# 01_-_POWER.net
KiCad netlist of a schematic drawn in Altium Designer
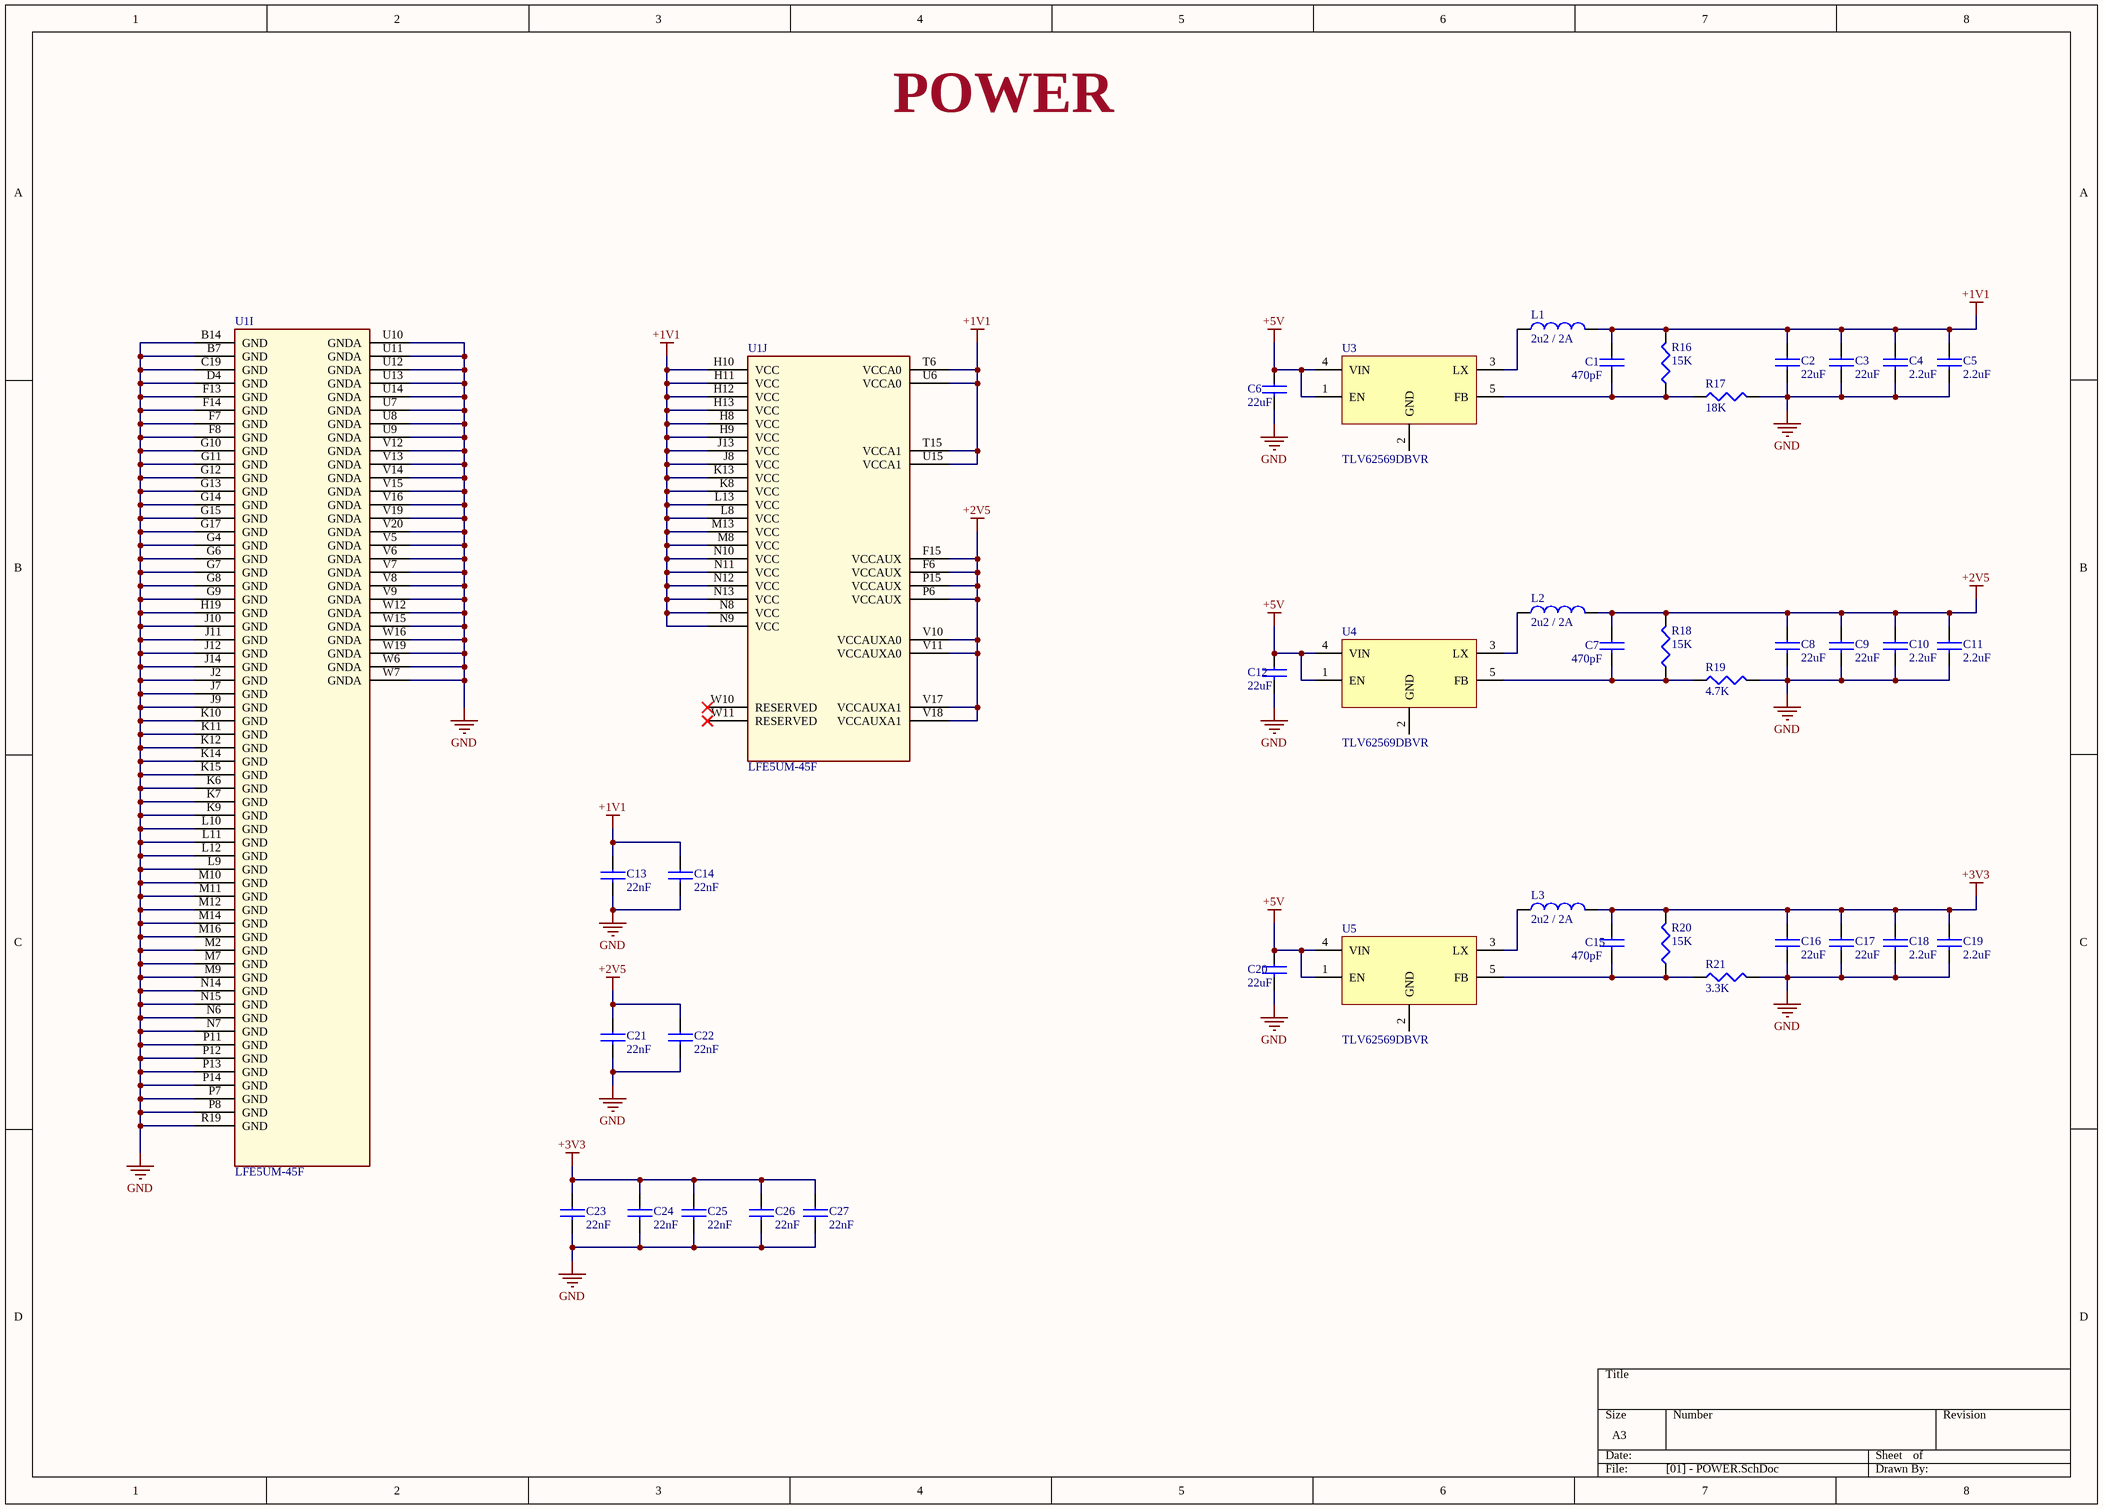
[diagram p0: [01] - POWER.SchDoc]

(export (version "E")
  (design (tool "Eeschema 10.0.6"))
  (components
    (comp (ref "C1")
      (value "470pF")
      (footprint "C0603")
      (fields
        (field (name "MANUFACTURER") "KEMET")
        (field (name "MANUFACTURER PART NUMBER") "C0603C471K3RACTU")
        (field (name "TOLERANCE") "10%")
      )
      (libsource (lib "ECP5_V2") (part "C0603C471K3RACTU"))
    )
    (comp (ref "C2")
      (value "22uF")
      (footprint "C0805")
      (description "CAP CER 22UF 6.3V X5R 0805")
      (fields
        (field (name "MANUFACTURER") "Samsung")
        (field (name "MANUFACTURER PART NUMBER") "CL21A226MQCLRNC")
      )
      (libsource (lib "ECP5_V2") (part "CL21A226MQCLRNC"))
    )
    (comp (ref "C3")
      (value "22uF")
      (footprint "C0805")
      (description "CAP CER 22UF 6.3V X5R 0805")
      (fields
        (field (name "MANUFACTURER") "Samsung")
        (field (name "MANUFACTURER PART NUMBER") "CL21A226MQCLRNC")
      )
      (libsource (lib "ECP5_V2") (part "CL21A226MQCLRNC"))
    )
    (comp (ref "C4")
      (value "2.2uF")
      (footprint "C0805")
      (description "Ceramic capacitor SMD 0805 2.2 µF 25 V 10 %")
      (fields
        (field (name "MANUFACTURER") "Samsung")
        (field (name "MANUFACTURER PART NUMBER") "CL21A225KAFNNNG")
      )
      (libsource (lib "ECP5_V2") (part "CL21A225KAFNNNG"))
    )
    (comp (ref "C5")
      (value "2.2uF")
      (footprint "C0805")
      (description "Ceramic capacitor SMD 0805 2.2 µF 25 V 10 %")
      (fields
        (field (name "MANUFACTURER") "Samsung")
        (field (name "MANUFACTURER PART NUMBER") "CL21A225KAFNNNG")
      )
      (libsource (lib "ECP5_V2") (part "CL21A225KAFNNNG"))
    )
    (comp (ref "C6")
      (value "22uF")
      (footprint "C0805")
      (description "CAP CER 22UF 6.3V X5R 0805")
      (fields
        (field (name "MANUFACTURER") "Samsung")
        (field (name "MANUFACTURER PART NUMBER") "CL21A226MQCLRNC")
      )
      (libsource (lib "ECP5_V2") (part "CL21A226MQCLRNC"))
    )
    (comp (ref "C7")
      (value "470pF")
      (footprint "C0603")
      (fields
        (field (name "MANUFACTURER") "KEMET")
        (field (name "MANUFACTURER PART NUMBER") "C0603C471K3RACTU")
        (field (name "TOLERANCE") "10%")
      )
      (libsource (lib "ECP5_V2") (part "C0603C471K3RACTU"))
    )
    (comp (ref "C8")
      (value "22uF")
      (footprint "C0805")
      (description "CAP CER 22UF 6.3V X5R 0805")
      (fields
        (field (name "MANUFACTURER") "Samsung")
        (field (name "MANUFACTURER PART NUMBER") "CL21A226MQCLRNC")
      )
      (libsource (lib "ECP5_V2") (part "CL21A226MQCLRNC"))
    )
    (comp (ref "C9")
      (value "22uF")
      (footprint "C0805")
      (description "CAP CER 22UF 6.3V X5R 0805")
      (fields
        (field (name "MANUFACTURER") "Samsung")
        (field (name "MANUFACTURER PART NUMBER") "CL21A226MQCLRNC")
      )
      (libsource (lib "ECP5_V2") (part "CL21A226MQCLRNC"))
    )
    (comp (ref "C10")
      (value "2.2uF")
      (footprint "C0805")
      (description "Ceramic capacitor SMD 0805 2.2 µF 25 V 10 %")
      (fields
        (field (name "MANUFACTURER") "Samsung")
        (field (name "MANUFACTURER PART NUMBER") "CL21A225KAFNNNG")
      )
      (libsource (lib "ECP5_V2") (part "CL21A225KAFNNNG"))
    )
    (comp (ref "C11")
      (value "2.2uF")
      (footprint "C0805")
      (description "Ceramic capacitor SMD 0805 2.2 µF 25 V 10 %")
      (fields
        (field (name "MANUFACTURER") "Samsung")
        (field (name "MANUFACTURER PART NUMBER") "CL21A225KAFNNNG")
      )
      (libsource (lib "ECP5_V2") (part "CL21A225KAFNNNG"))
    )
    (comp (ref "C12")
      (value "22uF")
      (footprint "C0805")
      (description "CAP CER 22UF 6.3V X5R 0805")
      (fields
        (field (name "MANUFACTURER") "Samsung")
        (field (name "MANUFACTURER PART NUMBER") "CL21A226MQCLRNC")
      )
      (libsource (lib "ECP5_V2") (part "CL21A226MQCLRNC"))
    )
    (comp (ref "C13")
      (value "22nF")
      (footprint "C0603")
      (description "Feed Through Capacitors 22nF X7R 20% 25V")
      (fields
        (field (name "MANUFACTURER") "Yageo")
        (field (name "MANUFACTURER PART NUMBER") "CX0603MRX7R8BB223")
      )
      (libsource (lib "ECP5_V2") (part "CX0603MRX7R8BB223"))
    )
    (comp (ref "C14")
      (value "22nF")
      (footprint "C0603")
      (description "Feed Through Capacitors 22nF X7R 20% 25V")
      (fields
        (field (name "MANUFACTURER") "Yageo")
        (field (name "MANUFACTURER PART NUMBER") "CX0603MRX7R8BB223")
      )
      (libsource (lib "ECP5_V2") (part "CX0603MRX7R8BB223"))
    )
    (comp (ref "C15")
      (value "470pF")
      (footprint "C0603")
      (fields
        (field (name "MANUFACTURER") "KEMET")
        (field (name "MANUFACTURER PART NUMBER") "C0603C471K3RACTU")
        (field (name "TOLERANCE") "10%")
      )
      (libsource (lib "ECP5_V2") (part "C0603C471K3RACTU"))
    )
    (comp (ref "C16")
      (value "22uF")
      (footprint "C0805")
      (description "CAP CER 22UF 6.3V X5R 0805")
      (fields
        (field (name "MANUFACTURER") "Samsung")
        (field (name "MANUFACTURER PART NUMBER") "CL21A226MQCLRNC")
      )
      (libsource (lib "ECP5_V2") (part "CL21A226MQCLRNC"))
    )
    (comp (ref "C17")
      (value "22uF")
      (footprint "C0805")
      (description "CAP CER 22UF 6.3V X5R 0805")
      (fields
        (field (name "MANUFACTURER") "Samsung")
        (field (name "MANUFACTURER PART NUMBER") "CL21A226MQCLRNC")
      )
      (libsource (lib "ECP5_V2") (part "CL21A226MQCLRNC"))
    )
    (comp (ref "C18")
      (value "2.2uF")
      (footprint "C0805")
      (description "Ceramic capacitor SMD 0805 2.2 µF 25 V 10 %")
      (fields
        (field (name "MANUFACTURER") "Samsung")
        (field (name "MANUFACTURER PART NUMBER") "CL21A225KAFNNNG")
      )
      (libsource (lib "ECP5_V2") (part "CL21A225KAFNNNG"))
    )
    (comp (ref "C19")
      (value "2.2uF")
      (footprint "C0805")
      (description "Ceramic capacitor SMD 0805 2.2 µF 25 V 10 %")
      (fields
        (field (name "MANUFACTURER") "Samsung")
        (field (name "MANUFACTURER PART NUMBER") "CL21A225KAFNNNG")
      )
      (libsource (lib "ECP5_V2") (part "CL21A225KAFNNNG"))
    )
    (comp (ref "C20")
      (value "22uF")
      (footprint "C0805")
      (description "CAP CER 22UF 6.3V X5R 0805")
      (fields
        (field (name "MANUFACTURER") "Samsung")
        (field (name "MANUFACTURER PART NUMBER") "CL21A226MQCLRNC")
      )
      (libsource (lib "ECP5_V2") (part "CL21A226MQCLRNC"))
    )
    (comp (ref "C21")
      (value "22nF")
      (footprint "C0603")
      (description "Feed Through Capacitors 22nF X7R 20% 25V")
      (fields
        (field (name "MANUFACTURER") "Yageo")
        (field (name "MANUFACTURER PART NUMBER") "CX0603MRX7R8BB223")
      )
      (libsource (lib "ECP5_V2") (part "CX0603MRX7R8BB223"))
    )
    (comp (ref "C22")
      (value "22nF")
      (footprint "C0603")
      (description "Feed Through Capacitors 22nF X7R 20% 25V")
      (fields
        (field (name "MANUFACTURER") "Yageo")
        (field (name "MANUFACTURER PART NUMBER") "CX0603MRX7R8BB223")
      )
      (libsource (lib "ECP5_V2") (part "CX0603MRX7R8BB223"))
    )
    (comp (ref "C23")
      (value "22nF")
      (footprint "C0603")
      (description "Feed Through Capacitors 22nF X7R 20% 25V")
      (fields
        (field (name "MANUFACTURER") "Yageo")
        (field (name "MANUFACTURER PART NUMBER") "CX0603MRX7R8BB223")
      )
      (libsource (lib "ECP5_V2") (part "CX0603MRX7R8BB223"))
    )
    (comp (ref "C24")
      (value "22nF")
      (footprint "C0603")
      (description "Feed Through Capacitors 22nF X7R 20% 25V")
      (fields
        (field (name "MANUFACTURER") "Yageo")
        (field (name "MANUFACTURER PART NUMBER") "CX0603MRX7R8BB223")
      )
      (libsource (lib "ECP5_V2") (part "CX0603MRX7R8BB223"))
    )
    (comp (ref "C25")
      (value "22nF")
      (footprint "C0603")
      (description "Feed Through Capacitors 22nF X7R 20% 25V")
      (fields
        (field (name "MANUFACTURER") "Yageo")
        (field (name "MANUFACTURER PART NUMBER") "CX0603MRX7R8BB223")
      )
      (libsource (lib "ECP5_V2") (part "CX0603MRX7R8BB223"))
    )
    (comp (ref "C26")
      (value "22nF")
      (footprint "C0603")
      (description "Feed Through Capacitors 22nF X7R 20% 25V")
      (fields
        (field (name "MANUFACTURER") "Yageo")
        (field (name "MANUFACTURER PART NUMBER") "CX0603MRX7R8BB223")
      )
      (libsource (lib "ECP5_V2") (part "CX0603MRX7R8BB223"))
    )
    (comp (ref "C27")
      (value "22nF")
      (footprint "C0603")
      (description "Feed Through Capacitors 22nF X7R 20% 25V")
      (fields
        (field (name "MANUFACTURER") "Yageo")
        (field (name "MANUFACTURER PART NUMBER") "CX0603MRX7R8BB223")
      )
      (libsource (lib "ECP5_V2") (part "CX0603MRX7R8BB223"))
    )
    (comp (ref "L1")
      (value "2u2 / 2A")
      (footprint "C1210_IND")
      (description "FIXED IND 2.2UH 2A 80 MOHM SMD")
      (fields
        (field (name "MANUFACTURER") "KEMET")
        (field (name "MANUFACTURER PART NUMBER") "L1210R2R2MDWIT")
      )
      (libsource (lib "ECP5_V2") (part "L1210R2R2MDWIT"))
    )
    (comp (ref "L2")
      (value "2u2 / 2A")
      (footprint "C1210_IND")
      (description "FIXED IND 2.2UH 2A 80 MOHM SMD")
      (fields
        (field (name "MANUFACTURER") "KEMET")
        (field (name "MANUFACTURER PART NUMBER") "L1210R2R2MDWIT")
      )
      (libsource (lib "ECP5_V2") (part "L1210R2R2MDWIT"))
    )
    (comp (ref "L3")
      (value "2u2 / 2A")
      (footprint "C1210_IND")
      (description "FIXED IND 2.2UH 2A 80 MOHM SMD")
      (fields
        (field (name "MANUFACTURER") "KEMET")
        (field (name "MANUFACTURER PART NUMBER") "L1210R2R2MDWIT")
      )
      (libsource (lib "ECP5_V2") (part "L1210R2R2MDWIT"))
    )
    (comp (ref "R16")
      (value "15K")
      (footprint "R0603")
      (description "Res Thick Film 0603 15K Ohm 1% 1/10W ?100ppm/?C Molded SMD Paper T/R")
      (fields
        (field (name "MANUFACTURER") "Yageo")
        (field (name "MANUFACTURER PART NUMBER") "RC0603FR-0715KL")
      )
      (libsource (lib "ECP5_V2") (part "RC0603FR-0715KL"))
    )
    (comp (ref "R17")
      (value "18K")
      (footprint "R0603")
      (fields
        (field (name "MANUFACTURER") "Yageo")
        (field (name "MANUFACTURER PART NUMBER") "RC0603FR-0718KL")
        (field (name "TOLERANCE") "1%")
      )
      (libsource (lib "ECP5_V2") (part "RC0603FR-0718KL"))
    )
    (comp (ref "R18")
      (value "15K")
      (footprint "R0603")
      (description "Res Thick Film 0603 15K Ohm 1% 1/10W ?100ppm/?C Molded SMD Paper T/R")
      (fields
        (field (name "MANUFACTURER") "Yageo")
        (field (name "MANUFACTURER PART NUMBER") "RC0603FR-0715KL")
      )
      (libsource (lib "ECP5_V2") (part "RC0603FR-0715KL"))
    )
    (comp (ref "R19")
      (value "4.7K")
      (footprint "R0603")
      (description "RES SMD 4.7K OHM 1% 1/10W 0603")
      (fields
        (field (name "MANUFACTURER") "Yageo")
        (field (name "MANUFACTURER PART NUMBER") "RC0603FR-074K7L")
      )
      (libsource (lib "ECP5_V2") (part "RC0603FR-074K7L"))
    )
    (comp (ref "R20")
      (value "15K")
      (footprint "R0603")
      (description "Res Thick Film 0603 15K Ohm 1% 1/10W ?100ppm/?C Molded SMD Paper T/R")
      (fields
        (field (name "MANUFACTURER") "Yageo")
        (field (name "MANUFACTURER PART NUMBER") "RC0603FR-0715KL")
      )
      (libsource (lib "ECP5_V2") (part "RC0603FR-0715KL"))
    )
    (comp (ref "R21")
      (value "3.3K")
      (footprint "R0603")
      (fields
        (field (name "MANUFACTURER") "Yageo")
        (field (name "MANUFACTURER PART NUMBER") "RC0603FR-073K3L")
        (field (name "TOLERANCE") "1%")
      )
      (libsource (lib "ECP5_V2") (part "RC0603FR-073K3L"))
    )
    (comp (ref "U1")
      (value "LFE5UM-45F")
      (footprint "LFE5BG381")
      (description "ECP5 Series 44 K LUTs 203 I/O 1.1 V Slow Surface Mount FPGA - CABGA-381")
      (fields
        (field (name "MANUFACTURER") "Lattice Semiconductor")
        (field (name "MANUFACTURER PART NUMBER") "LFE5UM-45F-6BG381C")
      )
      (libsource (lib "ECP5_V2") (part "LFE5UM-45F-6BG381C"))
    )
    (comp (ref "U3")
      (value "TLV62569DBVR")
      (footprint "SOT95P370X145-5N")
      (description "1-A HIGH EFFICIENCY STEP-DOWN")
      (fields (field (name "MANUFACTURER") "Texas Instruments"))
      (libsource (lib "ECP5_V2") (part "TLV62569DBVR"))
    )
    (comp (ref "U4")
      (value "TLV62569DBVR")
      (footprint "SOT95P370X145-5N")
      (description "1-A HIGH EFFICIENCY STEP-DOWN")
      (fields (field (name "MANUFACTURER") "Texas Instruments"))
      (libsource (lib "ECP5_V2") (part "TLV62569DBVR"))
    )
    (comp (ref "U5")
      (value "TLV62569DBVR")
      (footprint "SOT95P370X145-5N")
      (description "1-A HIGH EFFICIENCY STEP-DOWN")
      (fields (field (name "MANUFACTURER") "Texas Instruments"))
      (libsource (lib "ECP5_V2") (part "TLV62569DBVR"))
    )
  )
  (nets
    (net (code "1") (name "+1V1") (class "Default")
      (node (ref "C1") (pin "1") (pinfunction "1_1") (pintype "passive"))
      (node (ref "C13") (pin "1") (pinfunction "1_1") (pintype "passive"))
      (node (ref "C14") (pin "1") (pinfunction "1_1") (pintype "passive"))
      (node (ref "C2") (pin "1") (pinfunction "1_1") (pintype "passive"))
      (node (ref "C3") (pin "1") (pinfunction "1_1") (pintype "passive"))
      (node (ref "C4") (pin "1") (pinfunction "1_1") (pintype "passive"))
      (node (ref "C5") (pin "1") (pinfunction "1_1") (pintype "passive"))
      (node (ref "L1") (pin "2") (pinfunction "2_2") (pintype "passive"))
      (node (ref "R16") (pin "2") (pinfunction "2_2") (pintype "passive"))
      (node (ref "U1") (pin "H10") (pinfunction "VCC_H10") (pintype "power_in"))
      (node (ref "U1") (pin "H11") (pinfunction "VCC_H11") (pintype "power_in"))
      (node (ref "U1") (pin "H12") (pinfunction "VCC_H12") (pintype "power_in"))
      (node (ref "U1") (pin "H13") (pinfunction "VCC_H13") (pintype "power_in"))
      (node (ref "U1") (pin "H8") (pinfunction "VCC_H8") (pintype "power_in"))
      (node (ref "U1") (pin "H9") (pinfunction "VCC_H9") (pintype "power_in"))
      (node (ref "U1") (pin "J13") (pinfunction "VCC_J13") (pintype "power_in"))
      (node (ref "U1") (pin "J8") (pinfunction "VCC_J8") (pintype "power_in"))
      (node (ref "U1") (pin "K13") (pinfunction "VCC_K13") (pintype "power_in"))
      (node (ref "U1") (pin "K8") (pinfunction "VCC_K8") (pintype "power_in"))
      (node (ref "U1") (pin "L13") (pinfunction "VCC_L13") (pintype "power_in"))
      (node (ref "U1") (pin "L8") (pinfunction "VCC_L8") (pintype "power_in"))
      (node (ref "U1") (pin "M13") (pinfunction "VCC_M13") (pintype "power_in"))
      (node (ref "U1") (pin "M8") (pinfunction "VCC_M8") (pintype "power_in"))
      (node (ref "U1") (pin "N10") (pinfunction "VCC_N10") (pintype "power_in"))
      (node (ref "U1") (pin "N11") (pinfunction "VCC_N11") (pintype "power_in"))
      (node (ref "U1") (pin "N12") (pinfunction "VCC_N12") (pintype "power_in"))
      (node (ref "U1") (pin "N13") (pinfunction "VCC_N13") (pintype "power_in"))
      (node (ref "U1") (pin "N8") (pinfunction "VCC_N8") (pintype "power_in"))
      (node (ref "U1") (pin "N9") (pinfunction "VCC_N9") (pintype "power_in"))
      (node (ref "U1") (pin "T15") (pinfunction "VCCA1_T15") (pintype "power_in"))
      (node (ref "U1") (pin "T6") (pinfunction "VCCA0_T6") (pintype "power_in"))
      (node (ref "U1") (pin "U15") (pinfunction "VCCA1_U15") (pintype "power_in"))
      (node (ref "U1") (pin "U6") (pinfunction "VCCA0_U6") (pintype "power_in"))
    )
    (net (code "2") (name "+2V5") (class "Default")
      (node (ref "C10") (pin "1") (pinfunction "1_1") (pintype "passive"))
      (node (ref "C11") (pin "1") (pinfunction "1_1") (pintype "passive"))
      (node (ref "C21") (pin "1") (pinfunction "1_1") (pintype "passive"))
      (node (ref "C22") (pin "1") (pinfunction "1_1") (pintype "passive"))
      (node (ref "C7") (pin "1") (pinfunction "1_1") (pintype "passive"))
      (node (ref "C8") (pin "1") (pinfunction "1_1") (pintype "passive"))
      (node (ref "C9") (pin "1") (pinfunction "1_1") (pintype "passive"))
      (node (ref "L2") (pin "2") (pinfunction "2_2") (pintype "passive"))
      (node (ref "R18") (pin "2") (pinfunction "2_2") (pintype "passive"))
      (node (ref "U1") (pin "F15") (pinfunction "VCCAUX_F15") (pintype "power_in"))
      (node (ref "U1") (pin "F6") (pinfunction "VCCAUX_F6") (pintype "power_in"))
      (node (ref "U1") (pin "P15") (pinfunction "VCCAUX_P15") (pintype "power_in"))
      (node (ref "U1") (pin "P6") (pinfunction "VCCAUX_P6") (pintype "power_in"))
      (node (ref "U1") (pin "V10") (pinfunction "VCCAUXA0_V10") (pintype "power_in"))
      (node (ref "U1") (pin "V11") (pinfunction "VCCAUXA0_V11") (pintype "power_in"))
      (node (ref "U1") (pin "V17") (pinfunction "VCCAUXA1_V17") (pintype "power_in"))
      (node (ref "U1") (pin "V18") (pinfunction "VCCAUXA1_V18") (pintype "power_in"))
    )
    (net (code "3") (name "+3V3") (class "Default")
      (node (ref "C15") (pin "1") (pinfunction "1_1") (pintype "passive"))
      (node (ref "C16") (pin "1") (pinfunction "1_1") (pintype "passive"))
      (node (ref "C17") (pin "1") (pinfunction "1_1") (pintype "passive"))
      (node (ref "C18") (pin "1") (pinfunction "1_1") (pintype "passive"))
      (node (ref "C19") (pin "1") (pinfunction "1_1") (pintype "passive"))
      (node (ref "C23") (pin "1") (pinfunction "1_1") (pintype "passive"))
      (node (ref "C24") (pin "1") (pinfunction "1_1") (pintype "passive"))
      (node (ref "C25") (pin "1") (pinfunction "1_1") (pintype "passive"))
      (node (ref "C26") (pin "1") (pinfunction "1_1") (pintype "passive"))
      (node (ref "C27") (pin "1") (pinfunction "1_1") (pintype "passive"))
      (node (ref "L3") (pin "2") (pinfunction "2_2") (pintype "passive"))
      (node (ref "R20") (pin "2") (pinfunction "2_2") (pintype "passive"))
    )
    (net (code "4") (name "+5V") (class "Default")
      (node (ref "C12") (pin "1") (pinfunction "1_1") (pintype "passive"))
      (node (ref "C20") (pin "1") (pinfunction "1_1") (pintype "passive"))
      (node (ref "C6") (pin "1") (pinfunction "1_1") (pintype "passive"))
      (node (ref "U3") (pin "1") (pinfunction "EN_1") (pintype "passive"))
      (node (ref "U3") (pin "4") (pinfunction "VIN_4") (pintype "passive"))
      (node (ref "U4") (pin "1") (pinfunction "EN_1") (pintype "passive"))
      (node (ref "U4") (pin "4") (pinfunction "VIN_4") (pintype "passive"))
      (node (ref "U5") (pin "1") (pinfunction "EN_1") (pintype "passive"))
      (node (ref "U5") (pin "4") (pinfunction "VIN_4") (pintype "passive"))
    )
    (net (code "5") (name "GND") (class "Default")
      (node (ref "C10") (pin "2") (pinfunction "2_2") (pintype "passive"))
      (node (ref "C11") (pin "2") (pinfunction "2_2") (pintype "passive"))
      (node (ref "C12") (pin "2") (pinfunction "2_2") (pintype "passive"))
      (node (ref "C13") (pin "2") (pinfunction "2_2") (pintype "passive"))
      (node (ref "C14") (pin "2") (pinfunction "2_2") (pintype "passive"))
      (node (ref "C16") (pin "2") (pinfunction "2_2") (pintype "passive"))
      (node (ref "C17") (pin "2") (pinfunction "2_2") (pintype "passive"))
      (node (ref "C18") (pin "2") (pinfunction "2_2") (pintype "passive"))
      (node (ref "C19") (pin "2") (pinfunction "2_2") (pintype "passive"))
      (node (ref "C2") (pin "2") (pinfunction "2_2") (pintype "passive"))
      (node (ref "C20") (pin "2") (pinfunction "2_2") (pintype "passive"))
      (node (ref "C21") (pin "2") (pinfunction "2_2") (pintype "passive"))
      (node (ref "C22") (pin "2") (pinfunction "2_2") (pintype "passive"))
      (node (ref "C23") (pin "2") (pinfunction "2_2") (pintype "passive"))
      (node (ref "C24") (pin "2") (pinfunction "2_2") (pintype "passive"))
      (node (ref "C25") (pin "2") (pinfunction "2_2") (pintype "passive"))
      (node (ref "C26") (pin "2") (pinfunction "2_2") (pintype "passive"))
      (node (ref "C27") (pin "2") (pinfunction "2_2") (pintype "passive"))
      (node (ref "C3") (pin "2") (pinfunction "2_2") (pintype "passive"))
      (node (ref "C4") (pin "2") (pinfunction "2_2") (pintype "passive"))
      (node (ref "C5") (pin "2") (pinfunction "2_2") (pintype "passive"))
      (node (ref "C6") (pin "2") (pinfunction "2_2") (pintype "passive"))
      (node (ref "C8") (pin "2") (pinfunction "2_2") (pintype "passive"))
      (node (ref "C9") (pin "2") (pinfunction "2_2") (pintype "passive"))
      (node (ref "R17") (pin "2") (pinfunction "2_2") (pintype "passive"))
      (node (ref "R19") (pin "2") (pinfunction "2_2") (pintype "passive"))
      (node (ref "R21") (pin "2") (pinfunction "2_2") (pintype "passive"))
      (node (ref "U1") (pin "B14") (pinfunction "GND_B14") (pintype "power_in"))
      (node (ref "U1") (pin "B7") (pinfunction "GND_B7") (pintype "power_in"))
      (node (ref "U1") (pin "C19") (pinfunction "GND_C19") (pintype "power_in"))
      (node (ref "U1") (pin "D4") (pinfunction "GND_D4") (pintype "power_in"))
      (node (ref "U1") (pin "F13") (pinfunction "GND_F13") (pintype "power_in"))
      (node (ref "U1") (pin "F14") (pinfunction "GND_F14") (pintype "power_in"))
      (node (ref "U1") (pin "F7") (pinfunction "GND_F7") (pintype "power_in"))
      (node (ref "U1") (pin "F8") (pinfunction "GND_F8") (pintype "power_in"))
      (node (ref "U1") (pin "G10") (pinfunction "GND_G10") (pintype "power_in"))
      (node (ref "U1") (pin "G11") (pinfunction "GND_G11") (pintype "power_in"))
      (node (ref "U1") (pin "G12") (pinfunction "GND_G12") (pintype "power_in"))
      (node (ref "U1") (pin "G13") (pinfunction "GND_G13") (pintype "power_in"))
      (node (ref "U1") (pin "G14") (pinfunction "GND_G14") (pintype "power_in"))
      (node (ref "U1") (pin "G15") (pinfunction "GND_G15") (pintype "power_in"))
      (node (ref "U1") (pin "G17") (pinfunction "GND_G17") (pintype "power_in"))
      (node (ref "U1") (pin "G4") (pinfunction "GND_G4") (pintype "power_in"))
      (node (ref "U1") (pin "G6") (pinfunction "GND_G6") (pintype "power_in"))
      (node (ref "U1") (pin "G7") (pinfunction "GND_G7") (pintype "power_in"))
      (node (ref "U1") (pin "G8") (pinfunction "GND_G8") (pintype "power_in"))
      (node (ref "U1") (pin "G9") (pinfunction "GND_G9") (pintype "power_in"))
      (node (ref "U1") (pin "H19") (pinfunction "GND_H19") (pintype "power_in"))
      (node (ref "U1") (pin "J10") (pinfunction "GND_J10") (pintype "power_in"))
      (node (ref "U1") (pin "J11") (pinfunction "GND_J11") (pintype "power_in"))
      (node (ref "U1") (pin "J12") (pinfunction "GND_J12") (pintype "power_in"))
      (node (ref "U1") (pin "J14") (pinfunction "GND_J14") (pintype "power_in"))
      (node (ref "U1") (pin "J2") (pinfunction "GND_J2") (pintype "power_in"))
      (node (ref "U1") (pin "J7") (pinfunction "GND_J7") (pintype "power_in"))
      (node (ref "U1") (pin "J9") (pinfunction "GND_J9") (pintype "power_in"))
      (node (ref "U1") (pin "K10") (pinfunction "GND_K10") (pintype "power_in"))
      (node (ref "U1") (pin "K11") (pinfunction "GND_K11") (pintype "power_in"))
      (node (ref "U1") (pin "K12") (pinfunction "GND_K12") (pintype "power_in"))
      (node (ref "U1") (pin "K14") (pinfunction "GND_K14") (pintype "power_in"))
      (node (ref "U1") (pin "K15") (pinfunction "GND_K15") (pintype "power_in"))
      (node (ref "U1") (pin "K6") (pinfunction "GND_K6") (pintype "power_in"))
      (node (ref "U1") (pin "K7") (pinfunction "GND_K7") (pintype "power_in"))
      (node (ref "U1") (pin "K9") (pinfunction "GND_K9") (pintype "power_in"))
      (node (ref "U1") (pin "L10") (pinfunction "GND_L10") (pintype "power_in"))
      (node (ref "U1") (pin "L11") (pinfunction "GND_L11") (pintype "power_in"))
      (node (ref "U1") (pin "L12") (pinfunction "GND_L12") (pintype "power_in"))
      (node (ref "U1") (pin "L9") (pinfunction "GND_L9") (pintype "power_in"))
      (node (ref "U1") (pin "M10") (pinfunction "GND_M10") (pintype "power_in"))
      (node (ref "U1") (pin "M11") (pinfunction "GND_M11") (pintype "power_in"))
      (node (ref "U1") (pin "M12") (pinfunction "GND_M12") (pintype "power_in"))
      (node (ref "U1") (pin "M14") (pinfunction "GND_M14") (pintype "power_in"))
      (node (ref "U1") (pin "M16") (pinfunction "GND_M16") (pintype "power_in"))
      (node (ref "U1") (pin "M2") (pinfunction "GND_M2") (pintype "power_in"))
      (node (ref "U1") (pin "M7") (pinfunction "GND_M7") (pintype "power_in"))
      (node (ref "U1") (pin "M9") (pinfunction "GND_M9") (pintype "power_in"))
      (node (ref "U1") (pin "N14") (pinfunction "GND_N14") (pintype "power_in"))
      (node (ref "U1") (pin "N15") (pinfunction "GND_N15") (pintype "power_in"))
      (node (ref "U1") (pin "N6") (pinfunction "GND_N6") (pintype "power_in"))
      (node (ref "U1") (pin "N7") (pinfunction "GND_N7") (pintype "power_in"))
      (node (ref "U1") (pin "P11") (pinfunction "GND_P11") (pintype "power_in"))
      (node (ref "U1") (pin "P12") (pinfunction "GND_P12") (pintype "power_in"))
      (node (ref "U1") (pin "P13") (pinfunction "GND_P13") (pintype "power_in"))
      (node (ref "U1") (pin "P14") (pinfunction "GND_P14") (pintype "power_in"))
      (node (ref "U1") (pin "P7") (pinfunction "GND_P7") (pintype "power_in"))
      (node (ref "U1") (pin "P8") (pinfunction "GND_P8") (pintype "power_in"))
      (node (ref "U1") (pin "R19") (pinfunction "GND_R19") (pintype "power_in"))
      (node (ref "U1") (pin "U10") (pinfunction "GNDA_U10") (pintype "power_in"))
      (node (ref "U1") (pin "U11") (pinfunction "GNDA_U11") (pintype "power_in"))
      (node (ref "U1") (pin "U12") (pinfunction "GNDA_U12") (pintype "power_in"))
      (node (ref "U1") (pin "U13") (pinfunction "GNDA_U13") (pintype "power_in"))
      (node (ref "U1") (pin "U14") (pinfunction "GNDA_U14") (pintype "power_in"))
      (node (ref "U1") (pin "U7") (pinfunction "GNDA_U7") (pintype "power_in"))
      (node (ref "U1") (pin "U8") (pinfunction "GNDA_U8") (pintype "power_in"))
      (node (ref "U1") (pin "U9") (pinfunction "GNDA_U9") (pintype "power_in"))
      (node (ref "U1") (pin "V12") (pinfunction "GNDA_V12") (pintype "power_in"))
      (node (ref "U1") (pin "V13") (pinfunction "GNDA_V13") (pintype "power_in"))
      (node (ref "U1") (pin "V14") (pinfunction "GNDA_V14") (pintype "power_in"))
      (node (ref "U1") (pin "V15") (pinfunction "GNDA_V15") (pintype "power_in"))
      (node (ref "U1") (pin "V16") (pinfunction "GNDA_V16") (pintype "power_in"))
      (node (ref "U1") (pin "V19") (pinfunction "GNDA_V19") (pintype "power_in"))
      (node (ref "U1") (pin "V20") (pinfunction "GNDA_V20") (pintype "power_in"))
      (node (ref "U1") (pin "V5") (pinfunction "GNDA_V5") (pintype "power_in"))
      (node (ref "U1") (pin "V6") (pinfunction "GNDA_V6") (pintype "power_in"))
      (node (ref "U1") (pin "V7") (pinfunction "GNDA_V7") (pintype "power_in"))
      (node (ref "U1") (pin "V8") (pinfunction "GNDA_V8") (pintype "power_in"))
      (node (ref "U1") (pin "V9") (pinfunction "GNDA_V9") (pintype "power_in"))
      (node (ref "U1") (pin "W12") (pinfunction "GNDA_W12") (pintype "power_in"))
      (node (ref "U1") (pin "W15") (pinfunction "GNDA_W15") (pintype "power_in"))
      (node (ref "U1") (pin "W16") (pinfunction "GNDA_W16") (pintype "power_in"))
      (node (ref "U1") (pin "W19") (pinfunction "GNDA_W19") (pintype "power_in"))
      (node (ref "U1") (pin "W6") (pinfunction "GNDA_W6") (pintype "power_in"))
      (node (ref "U1") (pin "W7") (pinfunction "GNDA_W7") (pintype "power_in"))
    )
    (net (code "6") (name "Net-(U3-FB)") (class "Default")
      (node (ref "C1") (pin "2") (pinfunction "2_2") (pintype "passive"))
      (node (ref "R16") (pin "1") (pinfunction "1_1") (pintype "passive"))
      (node (ref "R17") (pin "1") (pinfunction "1_1") (pintype "passive"))
      (node (ref "U3") (pin "5") (pinfunction "FB_5") (pintype "passive"))
    )
    (net (code "7") (name "Net-(U3-LX)") (class "Default")
      (node (ref "L1") (pin "1") (pinfunction "1_1") (pintype "passive"))
      (node (ref "U3") (pin "3") (pinfunction "LX_3") (pintype "passive"))
    )
    (net (code "8") (name "Net-(U4-FB)") (class "Default")
      (node (ref "C7") (pin "2") (pinfunction "2_2") (pintype "passive"))
      (node (ref "R18") (pin "1") (pinfunction "1_1") (pintype "passive"))
      (node (ref "R19") (pin "1") (pinfunction "1_1") (pintype "passive"))
      (node (ref "U4") (pin "5") (pinfunction "FB_5") (pintype "passive"))
    )
    (net (code "9") (name "Net-(U4-LX)") (class "Default")
      (node (ref "L2") (pin "1") (pinfunction "1_1") (pintype "passive"))
      (node (ref "U4") (pin "3") (pinfunction "LX_3") (pintype "passive"))
    )
    (net (code "10") (name "Net-(U5-FB)") (class "Default")
      (node (ref "C15") (pin "2") (pinfunction "2_2") (pintype "passive"))
      (node (ref "R20") (pin "1") (pinfunction "1_1") (pintype "passive"))
      (node (ref "R21") (pin "1") (pinfunction "1_1") (pintype "passive"))
      (node (ref "U5") (pin "5") (pinfunction "FB_5") (pintype "passive"))
    )
    (net (code "11") (name "Net-(U5-LX)") (class "Default")
      (node (ref "L3") (pin "1") (pinfunction "1_1") (pintype "passive"))
      (node (ref "U5") (pin "3") (pinfunction "LX_3") (pintype "passive"))
    )
    (net (code "12") (name "unconnected-(U1J-RESERVED-PadW10)") (class "Default")
      (node (ref "U1") (pin "W10") (pinfunction "RESERVED_W10") (pintype "power_in+no_connect"))
    )
    (net (code "13") (name "unconnected-(U1J-RESERVED-PadW11)") (class "Default")
      (node (ref "U1") (pin "W11") (pinfunction "RESERVED_W11") (pintype "power_in+no_connect"))
    )
    (net (code "14") (name "unconnected-(U3-GND-Pad2)") (class "Default")
      (node (ref "U3") (pin "2") (pinfunction "GND_2") (pintype "passive"))
    )
    (net (code "15") (name "unconnected-(U4-GND-Pad2)") (class "Default")
      (node (ref "U4") (pin "2") (pinfunction "GND_2") (pintype "passive"))
    )
    (net (code "16") (name "unconnected-(U5-GND-Pad2)") (class "Default")
      (node (ref "U5") (pin "2") (pinfunction "GND_2") (pintype "passive"))
    )
  )
)
